# AEBS_component_Front.net
KiCad netlist of a schematic drawn in Altium Designer
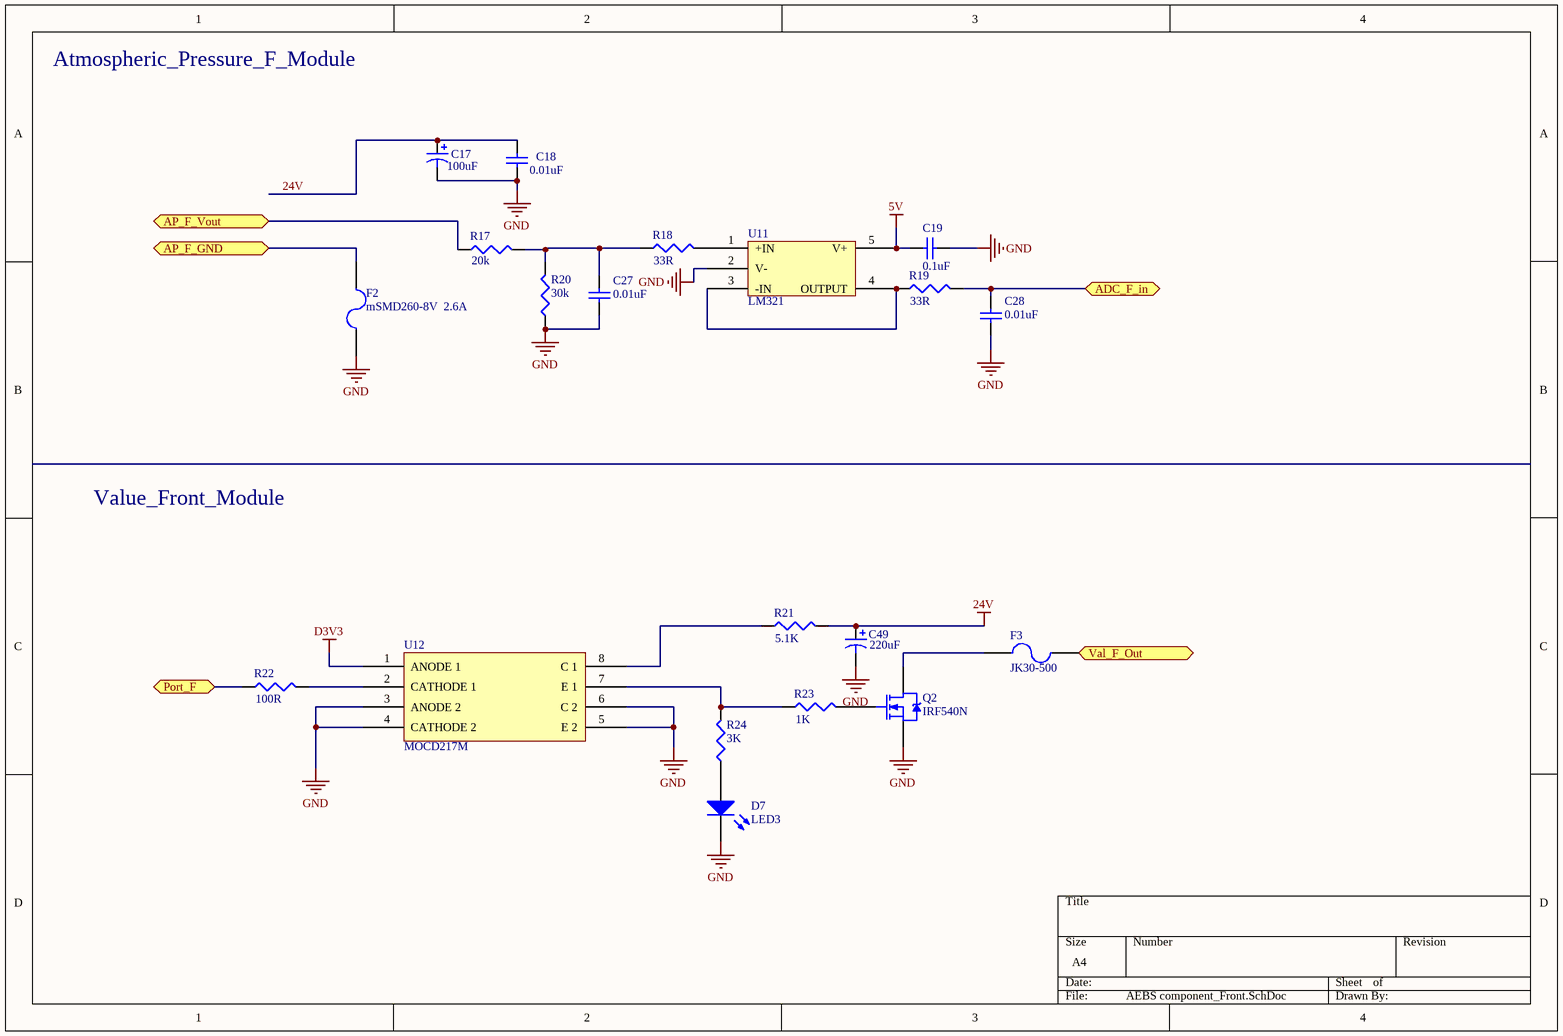
[diagram p0: AEBS component_Front.SchDoc]

(export (version "E")
  (design (tool "Eeschema 10.0.6"))
  (components
    (comp (ref "C17")
      (value "100uF")
      (footprint "C0805")
      (description "Polarized Capacitor (Surface Mount)")
      (fields (field (name "Comment") "Cap Pol3") (field (name "PUBLISHER") "Altium Limited"))
      (libsource (lib "Miscellaneous Devices") (part "Cap Pol3"))
    )
    (comp (ref "C18")
      (value "0.01uF")
      (footprint "C1206")
      (description "Capacitor (Semiconductor SIM Model)")
      (fields (field (name "Comment") "Cap Semi") (field (name "PUBLISHER") "Altium Limited"))
      (libsource (lib "Miscellaneous Devices") (part "Cap Semi"))
    )
    (comp (ref "C19")
      (value "0.1uF")
      (footprint "1608[0603]")
      (description "Capacitor (Semiconductor SIM Model)")
      (fields (field (name "Comment") "Cap Semi") (field (name "PUBLISHER") "Altium Limited"))
      (libsource (lib "Miscellaneous Devices") (part "Cap Semi"))
    )
    (comp (ref "C27")
      (value "0.01uF")
      (footprint "1608[0603]")
      (description "Capacitor (Semiconductor SIM Model)")
      (fields (field (name "Comment") "Cap Semi") (field (name "PUBLISHER") "Altium Limited"))
      (libsource (lib "Miscellaneous Devices") (part "Cap Semi"))
    )
    (comp (ref "C28")
      (value "0.01uF")
      (footprint "1608[0603]")
      (description "Capacitor (Semiconductor SIM Model)")
      (fields (field (name "Comment") "Cap Semi") (field (name "PUBLISHER") "Altium Limited"))
      (libsource (lib "Miscellaneous Devices") (part "Cap Semi"))
    )
    (comp (ref "C49")
      (value "220uF")
      (footprint "hg:Cap_pol_8*10.2")
      (description "Polarized Capacitor (Radial)")
      (fields (field (name "Comment") "Cap Pol1") (field (name "PUBLISHER") "Altium Limited"))
      (libsource (lib "Miscellaneous Devices") (part "Cap Pol1"))
    )
    (comp (ref "D7")
      (value "LED3")
      (footprint "hg:1206")
      (description "Typical BLUE SiC LED")
      (fields (field (name "PUBLISHER") "Altium Limited"))
      (libsource (lib "Miscellaneous Devices") (part "LED3"))
    )
    (comp (ref "F2")
      (value "mSMD260-8V  2.6A")
      (footprint "1812")
      (description "Fuse")
      (fields (field (name "PUBLISHER") "Altium Limited"))
      (libsource (lib "Miscellaneous Devices") (part "Fuse 2"))
    )
    (comp (ref "F3")
      (value "JK30-500")
      (footprint "hg:JK30-500")
      (description "Fuse")
      (fields (field (name "PUBLISHER") "Altium Limited"))
      (libsource (lib "Miscellaneous Devices") (part "Fuse 2"))
    )
    (comp (ref "Q2")
      (value "IRF540N")
      (footprint "TO-220AB")
      (description "N-Channel Power MOSFET")
      (fields (field (name "PUBLISHER") "Altium Limited"))
      (libsource (lib "Miscellaneous Devices") (part "NMOS-2"))
    )
    (comp (ref "R17")
      (value "20k")
      (footprint "J1-0603")
      (description "Resistor")
      (fields (field (name "Comment") "Res3") (field (name "PUBLISHER") "Altium Limited"))
      (libsource (lib "Miscellaneous Devices") (part "Res3"))
    )
    (comp (ref "R18")
      (value "33R")
      (footprint "J1-0603")
      (description "Resistor")
      (fields (field (name "Comment") "Res3") (field (name "PUBLISHER") "Altium Limited"))
      (libsource (lib "Miscellaneous Devices") (part "Res3"))
    )
    (comp (ref "R19")
      (value "33R")
      (footprint "J1-0603")
      (description "Resistor")
      (fields (field (name "Comment") "Res3") (field (name "PUBLISHER") "Altium Limited"))
      (libsource (lib "Miscellaneous Devices") (part "Res3"))
    )
    (comp (ref "R20")
      (value "30k")
      (footprint "J1-0603")
      (description "Resistor")
      (fields (field (name "Comment") "Res3") (field (name "PUBLISHER") "Altium Limited"))
      (libsource (lib "Miscellaneous Devices") (part "Res3"))
    )
    (comp (ref "R21")
      (value "5.1K")
      (footprint "J1-0603")
      (description "Resistor")
      (fields (field (name "Comment") "Res3") (field (name "PUBLISHER") "Altium Limited"))
      (libsource (lib "Miscellaneous Devices") (part "Res3"))
    )
    (comp (ref "R22")
      (value "100R")
      (footprint "J1-0603")
      (description "Resistor")
      (fields (field (name "Comment") "Res3") (field (name "PUBLISHER") "Altium Limited"))
      (libsource (lib "Miscellaneous Devices") (part "Res3"))
    )
    (comp (ref "R23")
      (value "1K")
      (footprint "J1-0603")
      (description "Resistor")
      (fields (field (name "Comment") "Res3") (field (name "PUBLISHER") "Altium Limited"))
      (libsource (lib "Miscellaneous Devices") (part "Res3"))
    )
    (comp (ref "R24")
      (value "3K")
      (footprint "J1-0603")
      (description "Resistor")
      (fields (field (name "Comment") "Res3") (field (name "PUBLISHER") "Altium Limited"))
      (libsource (lib "Miscellaneous Devices") (part "Res3"))
    )
    (comp (ref "U11") (value "LM321") (footprint "hg:LM321") (libsource (lib "hg") (part "LM321")))
    (comp (ref "U12") (value "MOCD217M") (footprint "hg:MOCD217M") (libsource (lib "hg") (part "MOCD217M")))
  )
  (nets
    (net (code "1") (name "/ADC_F_in") (class "Default")
      (node (ref "C28") (pin "2") (pinfunction "2_2") (pintype "passive"))
      (node (ref "R19") (pin "2") (pinfunction "2_2") (pintype "passive"))
    )
    (net (code "2") (name "/AP_F_GND") (class "Default")
      (node (ref "F2") (pin "1") (pinfunction "1_1") (pintype "passive"))
    )
    (net (code "3") (name "/AP_F_Vout") (class "Default")
      (node (ref "R17") (pin "1") (pinfunction "1_1") (pintype "passive"))
    )
    (net (code "4") (name "/Port_F") (class "Default")
      (node (ref "R22") (pin "1") (pinfunction "1_1") (pintype "passive"))
    )
    (net (code "5") (name "/Val_F_Out") (class "Default")
      (node (ref "F3") (pin "2") (pinfunction "2_2") (pintype "passive"))
    )
    (net (code "6") (name "5V") (class "Default")
      (node (ref "C19") (pin "2") (pinfunction "2_2") (pintype "passive"))
      (node (ref "U11") (pin "5") (pinfunction "V+_5") (pintype "passive"))
    )
    (net (code "7") (name "24V") (class "Default")
      (node (ref "C17") (pin "1") (pinfunction "1_1") (pintype "passive"))
      (node (ref "C18") (pin "1") (pinfunction "1_1") (pintype "passive"))
      (node (ref "C49") (pin "1") (pinfunction "1_1") (pintype "passive"))
      (node (ref "R21") (pin "2") (pinfunction "2_2") (pintype "passive"))
    )
    (net (code "8") (name "D3V3") (class "Default")
      (node (ref "U12") (pin "1") (pinfunction "ANODE_1_1") (pintype "passive"))
    )
    (net (code "9") (name "GND") (class "Default")
      (node (ref "C17") (pin "2") (pinfunction "2_2") (pintype "passive"))
      (node (ref "C18") (pin "2") (pinfunction "2_2") (pintype "passive"))
      (node (ref "C19") (pin "1") (pinfunction "1_1") (pintype "passive"))
      (node (ref "C27") (pin "1") (pinfunction "1_1") (pintype "passive"))
      (node (ref "C28") (pin "1") (pinfunction "1_1") (pintype "passive"))
      (node (ref "C49") (pin "2") (pinfunction "2_2") (pintype "passive"))
      (node (ref "D7") (pin "2") (pinfunction "K_2") (pintype "passive"))
      (node (ref "F2") (pin "2") (pinfunction "2_2") (pintype "passive"))
      (node (ref "Q2") (pin "3") (pinfunction "S_3") (pintype "passive"))
      (node (ref "R20") (pin "1") (pinfunction "1_1") (pintype "passive"))
      (node (ref "U11") (pin "2") (pinfunction "V-_2") (pintype "passive"))
      (node (ref "U12") (pin "3") (pinfunction "ANODE_2_3") (pintype "passive"))
      (node (ref "U12") (pin "4") (pinfunction "CATHODE_2_4") (pintype "passive"))
      (node (ref "U12") (pin "5") (pinfunction "E_2_5") (pintype "passive"))
      (node (ref "U12") (pin "6") (pinfunction "C_2_6") (pintype "passive"))
    )
    (net (code "10") (name "Net-(C27-Pad2)") (class "Default")
      (node (ref "C27") (pin "2") (pinfunction "2_2") (pintype "passive"))
      (node (ref "R17") (pin "2") (pinfunction "2_2") (pintype "passive"))
      (node (ref "R18") (pin "1") (pinfunction "1_1") (pintype "passive"))
      (node (ref "R20") (pin "2") (pinfunction "2_2") (pintype "passive"))
    )
    (net (code "11") (name "Net-(D7-A)") (class "Default")
      (node (ref "D7") (pin "1") (pinfunction "A_1") (pintype "passive"))
      (node (ref "R24") (pin "1") (pinfunction "1_1") (pintype "passive"))
    )
    (net (code "12") (name "Net-(Q2-D)") (class "Default")
      (node (ref "F3") (pin "1") (pinfunction "1_1") (pintype "passive"))
      (node (ref "Q2") (pin "2") (pinfunction "D_2") (pintype "passive"))
    )
    (net (code "13") (name "Net-(Q2-G)") (class "Default")
      (node (ref "Q2") (pin "1") (pinfunction "G_1") (pintype "passive"))
      (node (ref "R23") (pin "2") (pinfunction "2_2") (pintype "passive"))
    )
    (net (code "14") (name "Net-(U11-+IN)") (class "Default")
      (node (ref "R18") (pin "2") (pinfunction "2_2") (pintype "passive"))
      (node (ref "U11") (pin "1") (pinfunction "+IN_1") (pintype "passive"))
    )
    (net (code "15") (name "Net-(U11--IN)") (class "Default")
      (node (ref "R19") (pin "1") (pinfunction "1_1") (pintype "passive"))
      (node (ref "U11") (pin "3") (pinfunction "-IN_3") (pintype "passive"))
      (node (ref "U11") (pin "4") (pinfunction "OUTPUT_4") (pintype "passive"))
    )
    (net (code "16") (name "Net-(U12-CATHODE_1)") (class "Default")
      (node (ref "R22") (pin "2") (pinfunction "2_2") (pintype "passive"))
      (node (ref "U12") (pin "2") (pinfunction "CATHODE_1_2") (pintype "passive"))
    )
    (net (code "17") (name "Net-(U12-C_1)") (class "Default")
      (node (ref "R21") (pin "1") (pinfunction "1_1") (pintype "passive"))
      (node (ref "U12") (pin "8") (pinfunction "C_1_8") (pintype "passive"))
    )
    (net (code "18") (name "Net-(U12-E_1)") (class "Default")
      (node (ref "R23") (pin "1") (pinfunction "1_1") (pintype "passive"))
      (node (ref "R24") (pin "2") (pinfunction "2_2") (pintype "passive"))
      (node (ref "U12") (pin "7") (pinfunction "E_1_7") (pintype "passive"))
    )
  )
)
